# esp32_master_board.net
KiCad netlist of a schematic drawn in EAGLE
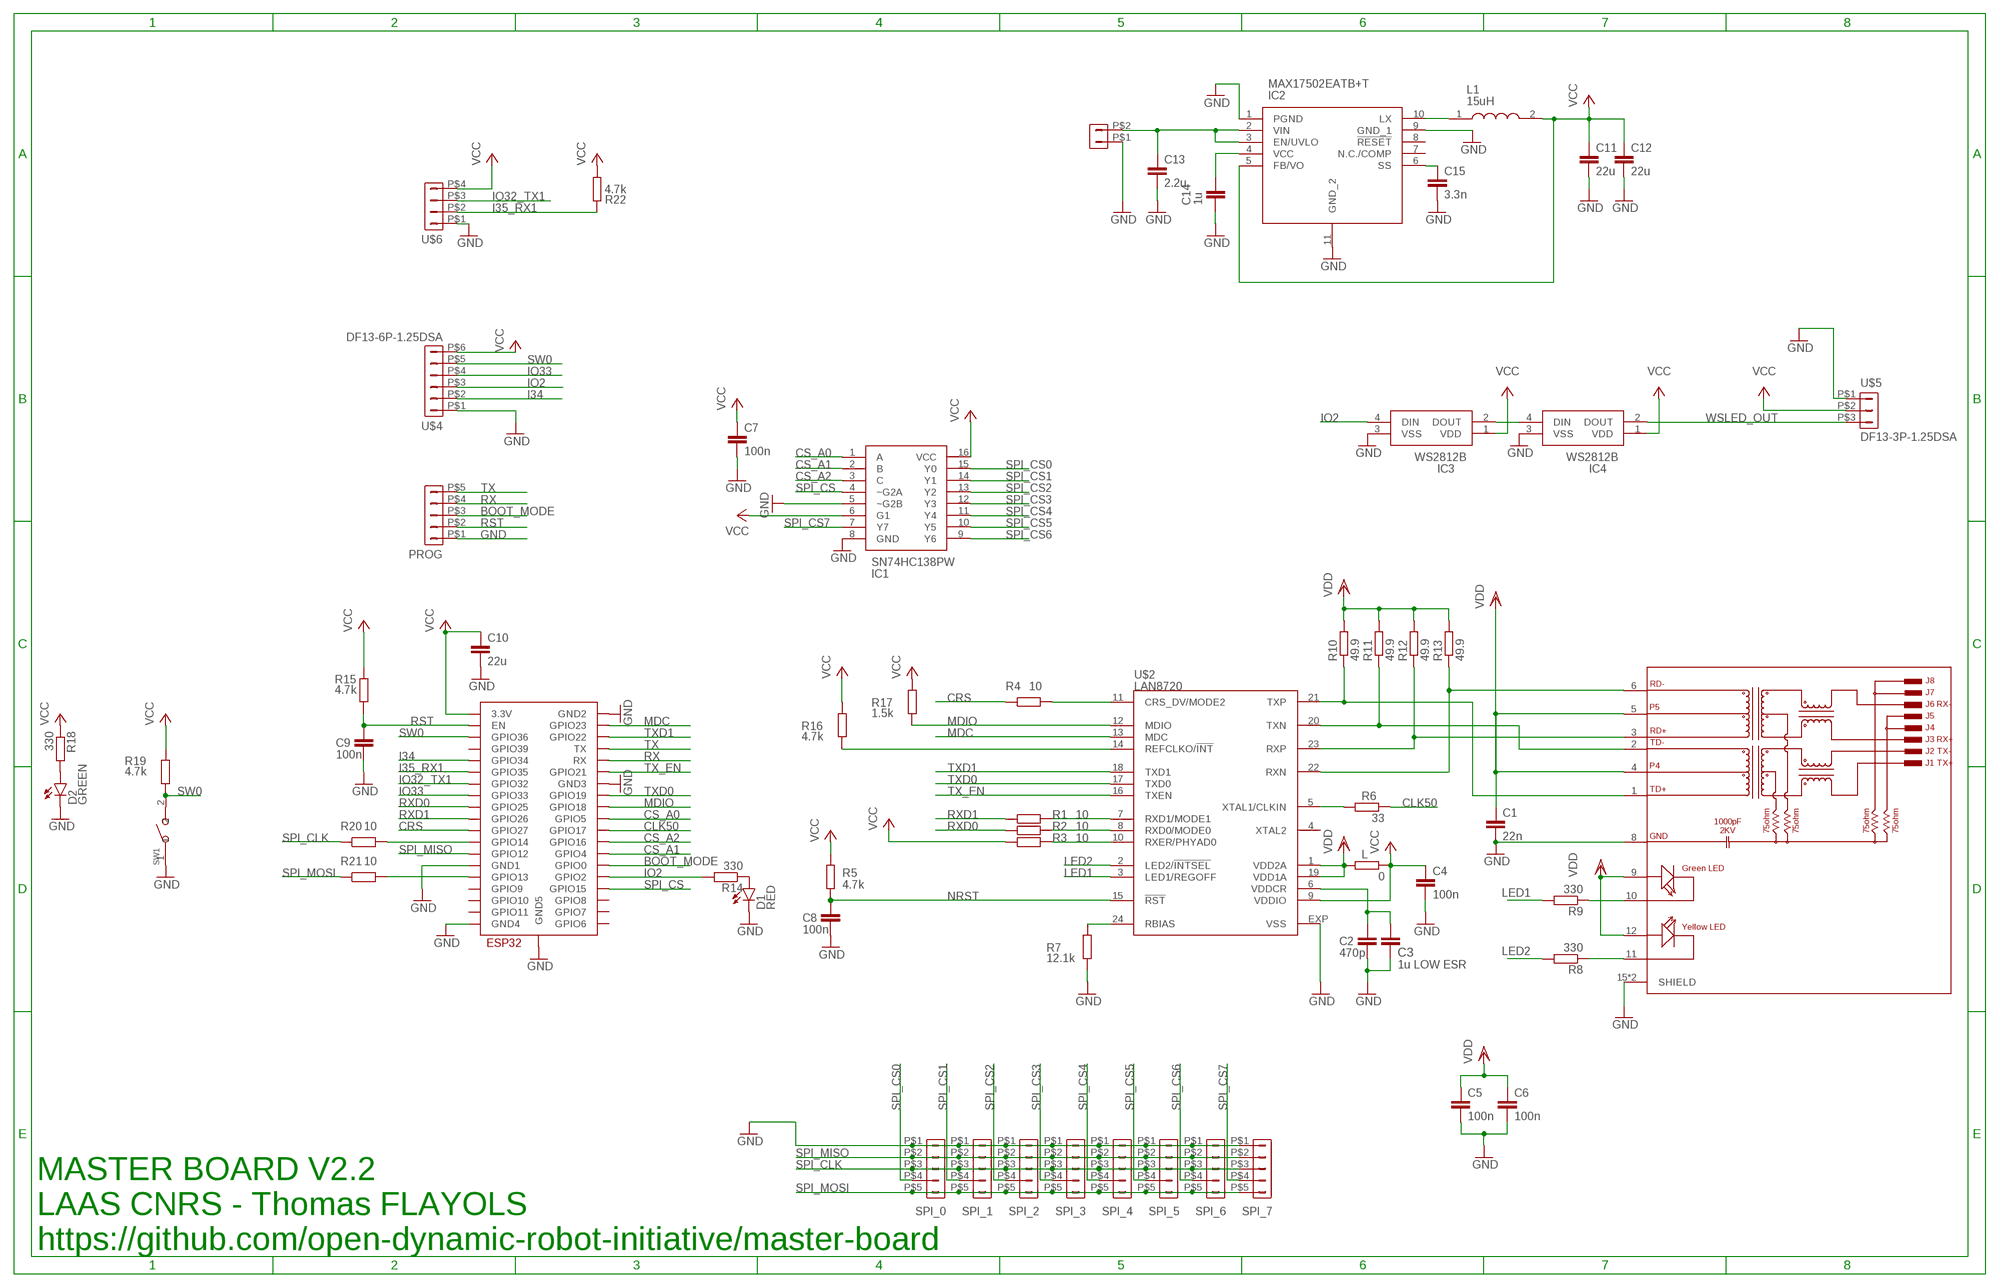
[diagram p0: schematic, sheet 1]

(export (version "E")
  (design (tool "Eeschema 10.0.6"))
  (components
    (comp (ref "C1")
      (value "22n")
      (footprint "eagle-import:0402")
      (fields (field (name "MANUFACTURER_PART_NUMBER") "885012205052"))
      (libsource (lib "eagle-import") (part "resistor_C-EUC0402"))
    )
    (comp (ref "C2")
      (value "470p")
      (footprint "eagle-import:0402")
      (fields (field (name "MANUFACTURER_PART_NUMBER") "CL05C471JB5NNNC"))
      (libsource (lib "eagle-import") (part "resistor_C-EUC0402"))
    )
    (comp (ref "C3")
      (value "1u LOW ESR")
      (footprint "eagle-import:0402")
      (fields (field (name "MANUFACTURER_PART_NUMBER") "CPL-CAP-X5R-0402-1UF-6.3V"))
      (libsource (lib "eagle-import") (part "resistor_C-EUC0402"))
    )
    (comp (ref "C4")
      (value "100n")
      (footprint "eagle-import:0402")
      (fields (field (name "MANUFACTURER_PART_NUMBER") "CPL-CAP-X7R-0402-100NF-16V"))
      (libsource (lib "eagle-import") (part "resistor_C-EUC0402"))
    )
    (comp (ref "C5")
      (value "100n")
      (footprint "eagle-import:0402")
      (fields (field (name "MANUFACTURER_PART_NUMBER") "CPL-CAP-X7R-0402-100NF-16V"))
      (libsource (lib "eagle-import") (part "resistor_C-EUC0402"))
    )
    (comp (ref "C6")
      (value "100n")
      (footprint "eagle-import:0402")
      (fields (field (name "MANUFACTURER_PART_NUMBER") "CPL-CAP-X7R-0402-100NF-16V"))
      (libsource (lib "eagle-import") (part "resistor_C-EUC0402"))
    )
    (comp (ref "C7")
      (value "100n")
      (footprint "eagle-import:0402")
      (fields (field (name "MANUFACTURER_PART_NUMBER") "CPL-CAP-X7R-0402-100NF-16V"))
      (libsource (lib "eagle-import") (part "resistor_C-EUC0402"))
    )
    (comp (ref "C8")
      (value "100n")
      (footprint "eagle-import:0402")
      (fields (field (name "MANUFACTURER_PART_NUMBER") "CPL-CAP-X7R-0402-100NF-16V"))
      (libsource (lib "eagle-import") (part "resistor_C-EUC0402"))
    )
    (comp (ref "C9")
      (value "100n")
      (footprint "eagle-import:0402")
      (fields (field (name "MANUFACTURER_PART_NUMBER") "CPL-CAP-X7R-0402-100NF-16V"))
      (libsource (lib "eagle-import") (part "resistor_C-EUC0402"))
    )
    (comp (ref "C10")
      (value "22u")
      (footprint "eagle-import:C0805")
      (fields (field (name "MANUFACTURER_PART_NUMBER") "CPL-CAP-X5R-0805-22UF-6.3V"))
      (libsource (lib "eagle-import") (part "C-EUC0805"))
    )
    (comp (ref "C11")
      (value "22u")
      (footprint "eagle-import:C0805")
      (fields (field (name "MANUFACTURER_PART_NUMBER") "CPL-CAP-X5R-0805-22UF-6.3V"))
      (libsource (lib "eagle-import") (part "C-EUC0805"))
    )
    (comp (ref "C12")
      (value "22u")
      (footprint "eagle-import:C0805")
      (fields (field (name "MANUFACTURER_PART_NUMBER") "CPL-CAP-X5R-0805-22UF-6.3V"))
      (libsource (lib "eagle-import") (part "C-EUC0805"))
    )
    (comp (ref "C13")
      (value "2.2u")
      (footprint "eagle-import:C1210")
      (fields (field (name "MANUFACTURER_PART_NUMBER") "C3225X7R1H225K250AB"))
      (libsource (lib "eagle-import") (part "resistor_C-EUC1210"))
    )
    (comp (ref "C14")
      (value "1u")
      (footprint "eagle-import:0402")
      (fields (field (name "MANUFACTURER_PART_NUMBER") "CPL-CAP-X5R-0402-1UF-6.3V"))
      (libsource (lib "eagle-import") (part "resistor_C-EUC0402"))
    )
    (comp (ref "C15")
      (value "3.3n")
      (footprint "eagle-import:0402")
      (fields (field (name "MANUFACTURER_PART_NUMBER") "885012205064"))
      (libsource (lib "eagle-import") (part "resistor_C-EUC0402"))
    )
    (comp (ref "D1")
      (value "RED")
      (footprint "eagle-import:CHIPLED_0603")
      (fields (field (name "MANUFACTURER_PART_NUMBER") "CPL-LED-0603-RED"))
      (libsource (lib "eagle-import") (part "LEDCHIPLED_0603"))
    )
    (comp (ref "D2")
      (value "GREEN")
      (footprint "eagle-import:CHIPLED_0603")
      (fields (field (name "MANUFACTURER_PART_NUMBER") "CPL-LED-0603-GREEN"))
      (libsource (lib "eagle-import") (part "LEDCHIPLED_0603"))
    )
    (comp (ref "IC1")
      (value "SN74HC138PW")
      (footprint "eagle-import:SOP65P640X120-16N")
      (fields (field (name "RS_PART_NUMBER") "6631928"))
      (libsource (lib "eagle-import") (part "SN74HC138PW"))
    )
    (comp (ref "IC2")
      (value "MAX17502EATB+T")
      (footprint "eagle-import:SON50P200X300X80-11N")
      (fields (field (name "MOUSER_PART_NUMBER") "700-MAX17502EATB+T"))
      (libsource (lib "eagle-import") (part "MAX17502EATB+T"))
    )
    (comp (ref "IC3")
      (value "WS2812B")
      (footprint "eagle-import:WS2812B")
      (libsource (lib "eagle-import") (part "WS2812B"))
    )
    (comp (ref "IC4")
      (value "WS2812B")
      (footprint "eagle-import:WS2812B")
      (libsource (lib "eagle-import") (part "WS2812B"))
    )
    (comp (ref "L")
      (value "0")
      (footprint "eagle-import:0402")
      (fields (field (name "MANUFACTURER_PART_NUMBER") "CPL-RES-0402-0-0.063W"))
      (libsource (lib "eagle-import") (part "R-EU_R0402"))
    )
    (comp (ref "L1")
      (value "15uH")
      (footprint "eagle-import:LPS6235")
      (fields
        (field (name "MANUFACTURER_PART_NUMBER") "LPS6235-153MRB")
        (field (name "MOUSER_PART_NUMBER") "994-LPS6235-153MRB")
      )
      (libsource (lib "eagle-import") (part "LPS6235-153MRB"))
    )
    (comp (ref "POWER")
      (value "DF13-2P-1.25DSA")
      (footprint "eagle-import:DF13-2P-1.25DSA")
      (fields (field (name "MANUFACTURER_PART_NUMBER") "DF13-3P-1.25DSA"))
      (libsource (lib "eagle-import") (part "DF13-2P-1.25DSA"))
    )
    (comp (ref "PROG")
      (value "DF13-5P-1.25DSA")
      (footprint "eagle-import:DF13-5P-1.25DSA")
      (libsource (lib "eagle-import") (part "DF13-5P-1.25DSA"))
    )
    (comp (ref "R1")
      (value "10")
      (footprint "eagle-import:0402")
      (fields (field (name "MANUFACTURER_PART_NUMBER") "CPL-RES-0402-10-0.063W"))
      (libsource (lib "eagle-import") (part "R-EU_R0402"))
    )
    (comp (ref "R2")
      (value "10")
      (footprint "eagle-import:0402")
      (fields (field (name "MANUFACTURER_PART_NUMBER") "CPL-RES-0402-10-0.063W"))
      (libsource (lib "eagle-import") (part "R-EU_R0402"))
    )
    (comp (ref "R3")
      (value "10")
      (footprint "eagle-import:0402")
      (fields (field (name "MANUFACTURER_PART_NUMBER") "CPL-RES-0402-10-0.063W"))
      (libsource (lib "eagle-import") (part "R-EU_R0402"))
    )
    (comp (ref "R4")
      (value "10")
      (footprint "eagle-import:0402")
      (fields (field (name "MANUFACTURER_PART_NUMBER") "CPL-RES-0402-10-0.063W"))
      (libsource (lib "eagle-import") (part "R-EU_R0402"))
    )
    (comp (ref "R5")
      (value "4.7k")
      (footprint "eagle-import:0402")
      (fields (field (name "MANUFACTURER_PART_NUMBER") "CPL-RES-0402-4.7K-0.063W"))
      (libsource (lib "eagle-import") (part "R-EU_R0402"))
    )
    (comp (ref "R6")
      (value "33")
      (footprint "eagle-import:0402")
      (fields (field (name "MANUFACTURER_PART_NUMBER") "CRCW040233R0FKEDC"))
      (libsource (lib "eagle-import") (part "R-EU_R0402"))
    )
    (comp (ref "R7")
      (value "12.1k")
      (footprint "eagle-import:0402")
      (fields (field (name "MANUFACTURER_PART_NUMBER") "ERJ-U02F1212X"))
      (libsource (lib "eagle-import") (part "R-EU_R0402"))
    )
    (comp (ref "R8")
      (value "330")
      (footprint "eagle-import:0402")
      (fields (field (name "MANUFACTURER_PART_NUMBER") "RC0402JR-13330RL"))
      (libsource (lib "eagle-import") (part "R-EU_R0402"))
    )
    (comp (ref "R9")
      (value "330")
      (footprint "eagle-import:0402")
      (fields (field (name "MANUFACTURER_PART_NUMBER") "RC0402JR-13330RL"))
      (libsource (lib "eagle-import") (part "R-EU_R0402"))
    )
    (comp (ref "R10")
      (value "49.9")
      (footprint "eagle-import:0402")
      (fields (field (name "MANUFACTURER_PART_NUMBER") "CRCW040249R9FKEDC"))
      (libsource (lib "eagle-import") (part "R-EU_R0402"))
    )
    (comp (ref "R11")
      (value "49.9")
      (footprint "eagle-import:0402")
      (fields (field (name "MANUFACTURER_PART_NUMBER") "CRCW040249R9FKEDC"))
      (libsource (lib "eagle-import") (part "R-EU_R0402"))
    )
    (comp (ref "R12")
      (value "49.9")
      (footprint "eagle-import:0402")
      (fields (field (name "MANUFACTURER_PART_NUMBER") "CRCW040249R9FKEDC"))
      (libsource (lib "eagle-import") (part "R-EU_R0402"))
    )
    (comp (ref "R13")
      (value "49.9")
      (footprint "eagle-import:0402")
      (fields (field (name "MANUFACTURER_PART_NUMBER") "CRCW040249R9FKEDC"))
      (libsource (lib "eagle-import") (part "R-EU_R0402"))
    )
    (comp (ref "R14")
      (value "330")
      (footprint "eagle-import:0402")
      (fields (field (name "MANUFACTURER_PART_NUMBER") "RC0402JR-13330RL"))
      (libsource (lib "eagle-import") (part "R-EU_R0402"))
    )
    (comp (ref "R15")
      (value "4.7k")
      (footprint "eagle-import:0402")
      (fields (field (name "MANUFACTURER_PART_NUMBER") "CPL-RES-0402-4.7K-0.063W"))
      (libsource (lib "eagle-import") (part "R-EU_R0402"))
    )
    (comp (ref "R16")
      (value "4.7k")
      (footprint "eagle-import:0402")
      (fields (field (name "MANUFACTURER_PART_NUMBER") "CPL-RES-0402-4.7K-0.063W"))
      (libsource (lib "eagle-import") (part "R-EU_R0402"))
    )
    (comp (ref "R17")
      (value "1.5k")
      (footprint "eagle-import:0402")
      (fields (field (name "MANUFACTURER_PART_NUMBER") "ERJ2GEJ152X"))
      (libsource (lib "eagle-import") (part "R-EU_R0402"))
    )
    (comp (ref "R18")
      (value "330")
      (footprint "eagle-import:0402")
      (fields (field (name "MANUFACTURER_PART_NUMBER") "RC0402JR-13330RL"))
      (libsource (lib "eagle-import") (part "R-EU_R0402"))
    )
    (comp (ref "R19")
      (value "4.7k")
      (footprint "eagle-import:0402")
      (fields (field (name "MANUFACTURER_PART_NUMBER") "CPL-RES-0402-4.7K-0.063W"))
      (libsource (lib "eagle-import") (part "R-EU_R0402"))
    )
    (comp (ref "R20")
      (value "10")
      (footprint "eagle-import:0402")
      (fields (field (name "MANUFACTURER_PART_NUMBER") "CPL-RES-0402-10-0.063W"))
      (libsource (lib "eagle-import") (part "R-EU_R0402"))
    )
    (comp (ref "R21")
      (value "10")
      (footprint "eagle-import:0402")
      (fields (field (name "MANUFACTURER_PART_NUMBER") "CPL-RES-0402-10-0.063W"))
      (libsource (lib "eagle-import") (part "R-EU_R0402"))
    )
    (comp (ref "R22")
      (value "4.7k")
      (footprint "eagle-import:0402")
      (fields (field (name "MANUFACTURER_PART_NUMBER") "CPL-RES-0402-4.7K-0.063W"))
      (libsource (lib "eagle-import") (part "R-EU_R0402"))
    )
    (comp (ref "SPI_0")
      (value "DF13-5P-1.25DSA")
      (footprint "eagle-import:DF13-5P-1.25DSA")
      (libsource (lib "eagle-import") (part "DF13-5P-1.25DSA"))
    )
    (comp (ref "SPI_1")
      (value "DF13-5P-1.25DSA")
      (footprint "eagle-import:DF13-5P-1.25DSA")
      (libsource (lib "eagle-import") (part "DF13-5P-1.25DSA"))
    )
    (comp (ref "SPI_2")
      (value "DF13-5P-1.25DSA")
      (footprint "eagle-import:DF13-5P-1.25DSA")
      (libsource (lib "eagle-import") (part "DF13-5P-1.25DSA"))
    )
    (comp (ref "SPI_3")
      (value "DF13-5P-1.25DSA")
      (footprint "eagle-import:DF13-5P-1.25DSA")
      (libsource (lib "eagle-import") (part "DF13-5P-1.25DSA"))
    )
    (comp (ref "SPI_4")
      (value "DF13-5P-1.25DSA")
      (footprint "eagle-import:DF13-5P-1.25DSA")
      (libsource (lib "eagle-import") (part "DF13-5P-1.25DSA"))
    )
    (comp (ref "SPI_5")
      (value "DF13-5P-1.25DSA")
      (footprint "eagle-import:DF13-5P-1.25DSA")
      (libsource (lib "eagle-import") (part "DF13-5P-1.25DSA"))
    )
    (comp (ref "SPI_6")
      (value "DF13-5P-1.25DSA")
      (footprint "eagle-import:DF13-5P-1.25DSA")
      (libsource (lib "eagle-import") (part "DF13-5P-1.25DSA"))
    )
    (comp (ref "SPI_7")
      (value "DF13-5P-1.25DSA")
      (footprint "eagle-import:DF13-5P-1.25DSA")
      (libsource (lib "eagle-import") (part "DF13-5P-1.25DSA"))
    )
    (comp (ref "SW1")
      (value "B3U-1000P-2P-SMD")
      (footprint "eagle-import:SW2-2.6-3.0X2.5X1.2+0.4MM")
      (fields (field (name "MANUFACTURER_PART_NUMBER") "B3U-1000P"))
      (libsource (lib "eagle-import") (part "SMD-BUTTON(2P-3.0X2.5X1.2+0.4MM)-B3U-1000P-2P-SMD"))
    )
    (comp (ref "U$1")
      (value "ESP32-WROOM")
      (footprint "eagle-import:ESP32-WROOM")
      (fields (field (name "MANUFACTURER_PART_NUMBER") "ESP32-WROOM-32D"))
      (libsource (lib "eagle-import") (part "ESP32-WROOM"))
    )
    (comp (ref "U$2")
      (value "LAN8720")
      (footprint "eagle-import:QFN24")
      (fields (field (name "MANUFACTURER_PART_NUMBER") "LAN8720A-CP"))
      (libsource (lib "eagle-import") (part "LAN8720"))
    )
    (comp (ref "U$3")
      (value "HR911105A")
      (footprint "eagle-import:HANRUN_HR911105A")
      (fields (field (name "MF") "DFRobot"))
      (libsource (lib "eagle-import") (part "HR911105A"))
    )
    (comp (ref "U$4")
      (value "DF13-6P-1.25DSA")
      (footprint "eagle-import:DF13-6P-1.25DSA")
      (libsource (lib "eagle-import") (part "DF13-6P-1.25DSA"))
    )
    (comp (ref "U$5")
      (value "DF13-3P-1.25DSA")
      (footprint "eagle-import:DF13-3P-1.25DSA")
      (libsource (lib "eagle-import") (part "DF13-3P-1.25DSA"))
    )
    (comp (ref "U$6")
      (value "DF13-4P-1.25DSA")
      (footprint "eagle-import:DF13-4P-1.25DSA")
      (libsource (lib "eagle-import") (part "DF13-4P-1.25DSA"))
    )
  )
  (nets
    (net (code "1") (name "/BOOT_MODE") (class "Default")
      (node (ref "PROG") (pin "P$3") (pinfunction "3_P$3") (pintype "passive"))
      (node (ref "U$1") (pin "IO0") (pinfunction "GPIO0_IO0") (pintype "bidirectional"))
    )
    (net (code "2") (name "/CLK50") (class "Default")
      (node (ref "R6") (pin "1") (pinfunction "1_1") (pintype "passive"))
      (node (ref "U$1") (pin "IO17") (pinfunction "GPIO17_IO17") (pintype "bidirectional"))
    )
    (net (code "3") (name "/CRS") (class "Default")
      (node (ref "R4") (pin "1") (pinfunction "1_1") (pintype "passive"))
      (node (ref "U$1") (pin "IO27") (pinfunction "GPIO27_IO27") (pintype "bidirectional"))
    )
    (net (code "4") (name "/CS_A0") (class "Default")
      (node (ref "IC1") (pin "1") (pinfunction "A_1") (pintype "bidirectional"))
      (node (ref "U$1") (pin "IO5") (pinfunction "GPIO5_IO5") (pintype "bidirectional"))
    )
    (net (code "5") (name "/CS_A1") (class "Default")
      (node (ref "IC1") (pin "2") (pinfunction "B_2") (pintype "bidirectional"))
      (node (ref "U$1") (pin "IO4") (pinfunction "GPIO4_IO4") (pintype "bidirectional"))
    )
    (net (code "6") (name "/CS_A2") (class "Default")
      (node (ref "IC1") (pin "3") (pinfunction "C_3") (pintype "bidirectional"))
      (node (ref "U$1") (pin "IO16") (pinfunction "GPIO16_IO16") (pintype "bidirectional"))
    )
    (net (code "7") (name "/I34") (class "Default")
      (node (ref "U$1") (pin "IO34") (pinfunction "GPIO34_IO34") (pintype "bidirectional"))
      (node (ref "U$4") (pin "P$2") (pinfunction "2_P$2") (pintype "passive"))
    )
    (net (code "8") (name "/I35_RX1") (class "Default")
      (node (ref "R22") (pin "2") (pinfunction "2_2") (pintype "passive"))
      (node (ref "U$1") (pin "IO35") (pinfunction "GPIO35_IO35") (pintype "bidirectional"))
      (node (ref "U$6") (pin "P$2") (pinfunction "2_P$2") (pintype "passive"))
    )
    (net (code "9") (name "/IO2") (class "Default")
      (node (ref "IC3") (pin "4") (pinfunction "DIN_4") (pintype "input"))
      (node (ref "R14") (pin "2") (pinfunction "2_2") (pintype "passive"))
      (node (ref "U$1") (pin "IO2") (pinfunction "GPIO2_IO2") (pintype "bidirectional"))
      (node (ref "U$4") (pin "P$3") (pinfunction "3_P$3") (pintype "passive"))
    )
    (net (code "10") (name "/IO32_TX1") (class "Default")
      (node (ref "U$1") (pin "IO32") (pinfunction "GPIO32_IO32") (pintype "bidirectional"))
      (node (ref "U$6") (pin "P$3") (pinfunction "3_P$3") (pintype "passive"))
    )
    (net (code "11") (name "/IO33") (class "Default")
      (node (ref "U$1") (pin "IO33") (pinfunction "GPIO33_IO33") (pintype "bidirectional"))
      (node (ref "U$4") (pin "P$4") (pinfunction "4_P$4") (pintype "passive"))
    )
    (net (code "12") (name "/LED1") (class "Default")
      (node (ref "R9") (pin "2") (pinfunction "2_2") (pintype "passive"))
      (node (ref "U$2") (pin "3") (pinfunction "LED1/REGOFF_3") (pintype "bidirectional"))
    )
    (net (code "13") (name "/LED2") (class "Default")
      (node (ref "R8") (pin "2") (pinfunction "2_2") (pintype "passive"))
      (node (ref "U$2") (pin "2") (pinfunction "LED2/~{INTSEL}_2") (pintype "bidirectional"))
    )
    (net (code "14") (name "/MDC") (class "Default")
      (node (ref "U$1") (pin "IO23") (pinfunction "GPIO23_IO23") (pintype "bidirectional"))
      (node (ref "U$2") (pin "13") (pinfunction "MDC_13") (pintype "bidirectional"))
    )
    (net (code "15") (name "/MDIO") (class "Default")
      (node (ref "R17") (pin "1") (pinfunction "1_1") (pintype "passive"))
      (node (ref "U$1") (pin "IO18") (pinfunction "GPIO18_IO18") (pintype "bidirectional"))
      (node (ref "U$2") (pin "12") (pinfunction "MDIO_12") (pintype "bidirectional"))
    )
    (net (code "16") (name "/NRST") (class "Default")
      (node (ref "C8") (pin "1") (pinfunction "1_1") (pintype "passive"))
      (node (ref "R5") (pin "1") (pinfunction "1_1") (pintype "passive"))
      (node (ref "U$2") (pin "15") (pinfunction "~{RST}_15") (pintype "bidirectional"))
    )
    (net (code "17") (name "/RST") (class "Default")
      (node (ref "C9") (pin "1") (pinfunction "1_1") (pintype "passive"))
      (node (ref "PROG") (pin "P$2") (pinfunction "2_P$2") (pintype "passive"))
      (node (ref "R15") (pin "1") (pinfunction "1_1") (pintype "passive"))
      (node (ref "U$1") (pin "EN") (pinfunction "EN_EN") (pintype "bidirectional"))
    )
    (net (code "18") (name "/RX") (class "Default")
      (node (ref "PROG") (pin "P$4") (pinfunction "4_P$4") (pintype "passive"))
      (node (ref "U$1") (pin "RX") (pinfunction "RX_RX") (pintype "bidirectional"))
    )
    (net (code "19") (name "/RXD0") (class "Default")
      (node (ref "R2") (pin "1") (pinfunction "1_1") (pintype "passive"))
      (node (ref "U$1") (pin "IO25") (pinfunction "GPIO25_IO25") (pintype "bidirectional"))
    )
    (net (code "20") (name "/RXD1") (class "Default")
      (node (ref "R1") (pin "1") (pinfunction "1_1") (pintype "passive"))
      (node (ref "U$1") (pin "IO26") (pinfunction "GPIO26_IO26") (pintype "bidirectional"))
    )
    (net (code "21") (name "/SPI_CLK") (class "Default")
      (node (ref "R20") (pin "1") (pinfunction "1_1") (pintype "passive"))
      (node (ref "SPI_0") (pin "P$3") (pinfunction "3_P$3") (pintype "passive"))
      (node (ref "SPI_1") (pin "P$3") (pinfunction "3_P$3") (pintype "passive"))
      (node (ref "SPI_2") (pin "P$3") (pinfunction "3_P$3") (pintype "passive"))
      (node (ref "SPI_3") (pin "P$3") (pinfunction "3_P$3") (pintype "passive"))
      (node (ref "SPI_4") (pin "P$3") (pinfunction "3_P$3") (pintype "passive"))
      (node (ref "SPI_5") (pin "P$3") (pinfunction "3_P$3") (pintype "passive"))
      (node (ref "SPI_6") (pin "P$3") (pinfunction "3_P$3") (pintype "passive"))
      (node (ref "SPI_7") (pin "P$3") (pinfunction "3_P$3") (pintype "passive"))
    )
    (net (code "22") (name "/SPI_CS") (class "Default")
      (node (ref "IC1") (pin "4") (pinfunction "~{G2A}_4") (pintype "bidirectional"))
      (node (ref "U$1") (pin "IO15") (pinfunction "GPIO15_IO15") (pintype "bidirectional"))
    )
    (net (code "23") (name "/SPI_CS0") (class "Default")
      (node (ref "IC1") (pin "15") (pinfunction "Y0_15") (pintype "bidirectional"))
      (node (ref "SPI_0") (pin "P$4") (pinfunction "4_P$4") (pintype "passive"))
    )
    (net (code "24") (name "/SPI_CS1") (class "Default")
      (node (ref "IC1") (pin "14") (pinfunction "Y1_14") (pintype "bidirectional"))
      (node (ref "SPI_1") (pin "P$4") (pinfunction "4_P$4") (pintype "passive"))
    )
    (net (code "25") (name "/SPI_CS2") (class "Default")
      (node (ref "IC1") (pin "13") (pinfunction "Y2_13") (pintype "bidirectional"))
      (node (ref "SPI_2") (pin "P$4") (pinfunction "4_P$4") (pintype "passive"))
    )
    (net (code "26") (name "/SPI_CS3") (class "Default")
      (node (ref "IC1") (pin "12") (pinfunction "Y3_12") (pintype "bidirectional"))
      (node (ref "SPI_3") (pin "P$4") (pinfunction "4_P$4") (pintype "passive"))
    )
    (net (code "27") (name "/SPI_CS4") (class "Default")
      (node (ref "IC1") (pin "11") (pinfunction "Y4_11") (pintype "bidirectional"))
      (node (ref "SPI_4") (pin "P$4") (pinfunction "4_P$4") (pintype "passive"))
    )
    (net (code "28") (name "/SPI_CS5") (class "Default")
      (node (ref "IC1") (pin "10") (pinfunction "Y5_10") (pintype "bidirectional"))
      (node (ref "SPI_5") (pin "P$4") (pinfunction "4_P$4") (pintype "passive"))
    )
    (net (code "29") (name "/SPI_CS6") (class "Default")
      (node (ref "IC1") (pin "9") (pinfunction "Y6_9") (pintype "bidirectional"))
      (node (ref "SPI_6") (pin "P$4") (pinfunction "4_P$4") (pintype "passive"))
    )
    (net (code "30") (name "/SPI_CS7") (class "Default")
      (node (ref "IC1") (pin "7") (pinfunction "Y7_7") (pintype "bidirectional"))
      (node (ref "SPI_7") (pin "P$4") (pinfunction "4_P$4") (pintype "passive"))
    )
    (net (code "31") (name "/SPI_MISO") (class "Default")
      (node (ref "SPI_0") (pin "P$2") (pinfunction "2_P$2") (pintype "passive"))
      (node (ref "SPI_1") (pin "P$2") (pinfunction "2_P$2") (pintype "passive"))
      (node (ref "SPI_2") (pin "P$2") (pinfunction "2_P$2") (pintype "passive"))
      (node (ref "SPI_3") (pin "P$2") (pinfunction "2_P$2") (pintype "passive"))
      (node (ref "SPI_4") (pin "P$2") (pinfunction "2_P$2") (pintype "passive"))
      (node (ref "SPI_5") (pin "P$2") (pinfunction "2_P$2") (pintype "passive"))
      (node (ref "SPI_6") (pin "P$2") (pinfunction "2_P$2") (pintype "passive"))
      (node (ref "SPI_7") (pin "P$2") (pinfunction "2_P$2") (pintype "passive"))
      (node (ref "U$1") (pin "IO12") (pinfunction "GPIO12_IO12") (pintype "bidirectional"))
    )
    (net (code "32") (name "/SPI_MOSI") (class "Default")
      (node (ref "R21") (pin "1") (pinfunction "1_1") (pintype "passive"))
      (node (ref "SPI_0") (pin "P$5") (pinfunction "5_P$5") (pintype "passive"))
      (node (ref "SPI_1") (pin "P$5") (pinfunction "5_P$5") (pintype "passive"))
      (node (ref "SPI_2") (pin "P$5") (pinfunction "5_P$5") (pintype "passive"))
      (node (ref "SPI_3") (pin "P$5") (pinfunction "5_P$5") (pintype "passive"))
      (node (ref "SPI_4") (pin "P$5") (pinfunction "5_P$5") (pintype "passive"))
      (node (ref "SPI_5") (pin "P$5") (pinfunction "5_P$5") (pintype "passive"))
      (node (ref "SPI_6") (pin "P$5") (pinfunction "5_P$5") (pintype "passive"))
      (node (ref "SPI_7") (pin "P$5") (pinfunction "5_P$5") (pintype "passive"))
    )
    (net (code "33") (name "/SW0") (class "Default")
      (node (ref "R19") (pin "1") (pinfunction "1_1") (pintype "passive"))
      (node (ref "SW1") (pin "2") (pinfunction "2_2") (pintype "bidirectional"))
      (node (ref "U$1") (pin "SENSOR_VP") (pinfunction "GPIO36_SENSOR_VP") (pintype "bidirectional"))
      (node (ref "U$4") (pin "P$5") (pinfunction "5_P$5") (pintype "passive"))
    )
    (net (code "34") (name "/TX") (class "Default")
      (node (ref "PROG") (pin "P$5") (pinfunction "5_P$5") (pintype "passive"))
      (node (ref "U$1") (pin "TX") (pinfunction "TX_TX") (pintype "bidirectional"))
    )
    (net (code "35") (name "/TXD0") (class "Default")
      (node (ref "U$1") (pin "IO19") (pinfunction "GPIO19_IO19") (pintype "bidirectional"))
      (node (ref "U$2") (pin "17") (pinfunction "TXD0_17") (pintype "bidirectional"))
    )
    (net (code "36") (name "/TXD1") (class "Default")
      (node (ref "U$1") (pin "IO22") (pinfunction "GPIO22_IO22") (pintype "bidirectional"))
      (node (ref "U$2") (pin "18") (pinfunction "TXD1_18") (pintype "bidirectional"))
    )
    (net (code "37") (name "/TX_EN") (class "Default")
      (node (ref "U$1") (pin "IO21") (pinfunction "GPIO21_IO21") (pintype "bidirectional"))
      (node (ref "U$2") (pin "16") (pinfunction "TXEN_16") (pintype "bidirectional"))
    )
    (net (code "38") (name "/WSLED_OUT") (class "Default")
      (node (ref "IC4") (pin "2") (pinfunction "DOUT_2") (pintype "output"))
      (node (ref "U$5") (pin "P$3") (pinfunction "3_P$3") (pintype "passive"))
    )
    (net (code "39") (name "GND") (class "Default")
      (node (ref "C1") (pin "2") (pinfunction "2_2") (pintype "passive"))
      (node (ref "C10") (pin "2") (pinfunction "2_2") (pintype "passive"))
      (node (ref "C11") (pin "2") (pinfunction "2_2") (pintype "passive"))
      (node (ref "C12") (pin "2") (pinfunction "2_2") (pintype "passive"))
      (node (ref "C13") (pin "2") (pinfunction "2_2") (pintype "passive"))
      (node (ref "C14") (pin "1") (pinfunction "1_1") (pintype "passive"))
      (node (ref "C15") (pin "2") (pinfunction "2_2") (pintype "passive"))
      (node (ref "C2") (pin "2") (pinfunction "2_2") (pintype "passive"))
      (node (ref "C3") (pin "2") (pinfunction "2_2") (pintype "passive"))
      (node (ref "C4") (pin "2") (pinfunction "2_2") (pintype "passive"))
      (node (ref "C5") (pin "2") (pinfunction "2_2") (pintype "passive"))
      (node (ref "C6") (pin "2") (pinfunction "2_2") (pintype "passive"))
      (node (ref "C7") (pin "2") (pinfunction "2_2") (pintype "passive"))
      (node (ref "C8") (pin "2") (pinfunction "2_2") (pintype "passive"))
      (node (ref "C9") (pin "2") (pinfunction "2_2") (pintype "passive"))
      (node (ref "D1") (pin "C") (pinfunction "C_C") (pintype "passive"))
      (node (ref "D2") (pin "C") (pinfunction "C_C") (pintype "passive"))
      (node (ref "IC1") (pin "5") (pinfunction "~{G2B}_5") (pintype "bidirectional"))
      (node (ref "IC1") (pin "8") (pinfunction "GND_8") (pintype "bidirectional"))
      (node (ref "IC2") (pin "1") (pinfunction "PGND_1") (pintype "bidirectional"))
      (node (ref "IC2") (pin "11") (pinfunction "GND_2_11") (pintype "bidirectional"))
      (node (ref "IC2") (pin "9") (pinfunction "GND_1_9") (pintype "bidirectional"))
      (node (ref "IC3") (pin "3") (pinfunction "VSS_3") (pintype "power_in"))
      (node (ref "IC4") (pin "3") (pinfunction "VSS_3") (pintype "power_in"))
      (node (ref "POWER") (pin "P$1") (pinfunction "1_P$1") (pintype "passive"))
      (node (ref "PROG") (pin "P$1") (pinfunction "1_P$1") (pintype "passive"))
      (node (ref "R7") (pin "1") (pinfunction "1_1") (pintype "passive"))
      (node (ref "SPI_0") (pin "P$1") (pinfunction "1_P$1") (pintype "passive"))
      (node (ref "SPI_1") (pin "P$1") (pinfunction "1_P$1") (pintype "passive"))
      (node (ref "SPI_2") (pin "P$1") (pinfunction "1_P$1") (pintype "passive"))
      (node (ref "SPI_3") (pin "P$1") (pinfunction "1_P$1") (pintype "passive"))
      (node (ref "SPI_4") (pin "P$1") (pinfunction "1_P$1") (pintype "passive"))
      (node (ref "SPI_5") (pin "P$1") (pinfunction "1_P$1") (pintype "passive"))
      (node (ref "SPI_6") (pin "P$1") (pinfunction "1_P$1") (pintype "passive"))
      (node (ref "SPI_7") (pin "P$1") (pinfunction "1_P$1") (pintype "passive"))
      (node (ref "SW1") (pin "1") (pinfunction "1_1") (pintype "bidirectional"))
      (node (ref "U$1") (pin "GND1") (pinfunction "GND1_GND1") (pintype "bidirectional"))
      (node (ref "U$1") (pin "GND2") (pinfunction "GND2_GND2") (pintype "bidirectional"))
      (node (ref "U$1") (pin "GND3") (pinfunction "GND3_GND3") (pintype "bidirectional"))
      (node (ref "U$1") (pin "GND4") (pinfunction "GND4_GND4") (pintype "bidirectional"))
      (node (ref "U$1") (pin "GND5") (pinfunction "GND5_GND5") (pintype "bidirectional"))
      (node (ref "U$2") (pin "EXP") (pinfunction "VSS_EXP") (pintype "power_in"))
      (node (ref "U$3") (pin "15") (pinfunction "SHIELD_15") (pintype "passive"))
      (node (ref "U$3") (pin "16") (pinfunction "SHIELD_16") (pintype "passive"))
      (node (ref "U$3") (pin "8") (pinfunction "GND_8") (pintype "power_in"))
      (node (ref "U$4") (pin "P$1") (pinfunction "1_P$1") (pintype "passive"))
      (node (ref "U$5") (pin "P$1") (pinfunction "1_P$1") (pintype "passive"))
      (node (ref "U$6") (pin "P$1") (pinfunction "1_P$1") (pintype "passive"))
    )
    (net (code "40") (name "Net-(D1-PadA)") (class "Default")
      (node (ref "D1") (pin "A") (pinfunction "A_A") (pintype "passive"))
      (node (ref "R14") (pin "1") (pinfunction "1_1") (pintype "passive"))
    )
    (net (code "41") (name "Net-(D2-PadA)") (class "Default")
      (node (ref "D2") (pin "A") (pinfunction "A_A") (pintype "passive"))
      (node (ref "R18") (pin "2") (pinfunction "2_2") (pintype "passive"))
    )
    (net (code "42") (name "Net-(IC2-EN{slash}UVLO)") (class "Default")
      (node (ref "C13") (pin "1") (pinfunction "1_1") (pintype "passive"))
      (node (ref "IC2") (pin "2") (pinfunction "VIN_2") (pintype "bidirectional"))
      (node (ref "IC2") (pin "3") (pinfunction "EN/UVLO_3") (pintype "bidirectional"))
      (node (ref "POWER") (pin "P$2") (pinfunction "2_P$2") (pintype "passive"))
    )
    (net (code "43") (name "Net-(IC2-LX)") (class "Default")
      (node (ref "IC2") (pin "10") (pinfunction "LX_10") (pintype "bidirectional"))
      (node (ref "L1") (pin "1") (pinfunction "1_1") (pintype "bidirectional"))
    )
    (net (code "44") (name "Net-(IC2-SS)") (class "Default")
      (node (ref "C15") (pin "1") (pinfunction "1_1") (pintype "passive"))
      (node (ref "IC2") (pin "6") (pinfunction "SS_6") (pintype "bidirectional"))
    )
    (net (code "45") (name "Net-(IC2-VCC)") (class "Default")
      (node (ref "C14") (pin "2") (pinfunction "2_2") (pintype "passive"))
      (node (ref "IC2") (pin "4") (pinfunction "VCC_4") (pintype "bidirectional"))
    )
    (net (code "46") (name "Net-(IC3-DOUT)") (class "Default")
      (node (ref "IC3") (pin "2") (pinfunction "DOUT_2") (pintype "output"))
      (node (ref "IC4") (pin "4") (pinfunction "DIN_4") (pintype "input"))
    )
    (net (code "47") (name "Net-(U$1-GPIO13)") (class "Default")
      (node (ref "R21") (pin "2") (pinfunction "2_2") (pintype "passive"))
      (node (ref "U$1") (pin "IO13") (pinfunction "GPIO13_IO13") (pintype "bidirectional"))
    )
    (net (code "48") (name "Net-(U$1-GPIO14)") (class "Default")
      (node (ref "R20") (pin "2") (pinfunction "2_2") (pintype "passive"))
      (node (ref "U$1") (pin "IO14") (pinfunction "GPIO14_IO14") (pintype "bidirectional"))
    )
    (net (code "49") (name "Net-(U$2-CRS_DV{slash}MODE2)") (class "Default")
      (node (ref "R4") (pin "2") (pinfunction "2_2") (pintype "passive"))
      (node (ref "U$2") (pin "11") (pinfunction "CRS_DV/MODE2_11") (pintype "bidirectional"))
    )
    (net (code "50") (name "Net-(U$2-RBIAS)") (class "Default")
      (node (ref "R7") (pin "2") (pinfunction "2_2") (pintype "passive"))
      (node (ref "U$2") (pin "24") (pinfunction "RBIAS_24") (pintype "bidirectional"))
    )
    (net (code "51") (name "Net-(U$2-REFCLKO{slash}~{INT})") (class "Default")
      (node (ref "R16") (pin "1") (pinfunction "1_1") (pintype "passive"))
      (node (ref "U$2") (pin "14") (pinfunction "REFCLKO/~{INT}_14") (pintype "bidirectional"))
    )
    (net (code "52") (name "Net-(U$2-RXD0{slash}MODE0)") (class "Default")
      (node (ref "R2") (pin "2") (pinfunction "2_2") (pintype "passive"))
      (node (ref "U$2") (pin "8") (pinfunction "RXD0/MODE0_8") (pintype "bidirectional"))
    )
    (net (code "53") (name "Net-(U$2-RXD1{slash}MODE1)") (class "Default")
      (node (ref "R1") (pin "2") (pinfunction "2_2") (pintype "passive"))
      (node (ref "U$2") (pin "7") (pinfunction "RXD1/MODE1_7") (pintype "bidirectional"))
    )
    (net (code "54") (name "Net-(U$2-RXER{slash}PHYAD0)") (class "Default")
      (node (ref "R3") (pin "2") (pinfunction "2_2") (pintype "passive"))
      (node (ref "U$2") (pin "10") (pinfunction "RXER/PHYAD0_10") (pintype "bidirectional"))
    )
    (net (code "55") (name "Net-(U$2-RXN)") (class "Default")
      (node (ref "R13") (pin "1") (pinfunction "1_1") (pintype "passive"))
      (node (ref "U$2") (pin "22") (pinfunction "RXN_22") (pintype "bidirectional"))
      (node (ref "U$3") (pin "6") (pinfunction "RD-_6") (pintype "passive"))
    )
    (net (code "56") (name "Net-(U$2-RXP)") (class "Default")
      (node (ref "R12") (pin "1") (pinfunction "1_1") (pintype "passive"))
      (node (ref "U$2") (pin "23") (pinfunction "RXP_23") (pintype "bidirectional"))
      (node (ref "U$3") (pin "3") (pinfunction "RD+_3") (pintype "passive"))
    )
    (net (code "57") (name "Net-(U$2-TXN)") (class "Default")
      (node (ref "R11") (pin "1") (pinfunction "1_1") (pintype "passive"))
      (node (ref "U$2") (pin "20") (pinfunction "TXN_20") (pintype "bidirectional"))
      (node (ref "U$3") (pin "2") (pinfunction "TD-_2") (pintype "passive"))
    )
    (net (code "58") (name "Net-(U$2-TXP)") (class "Default")
      (node (ref "R10") (pin "1") (pinfunction "1_1") (pintype "passive"))
      (node (ref "U$2") (pin "21") (pinfunction "TXP_21") (pintype "bidirectional"))
      (node (ref "U$3") (pin "1") (pinfunction "TD+_1") (pintype "passive"))
    )
    (net (code "59") (name "Net-(U$2-VDDCR)") (class "Default")
      (node (ref "C2") (pin "1") (pinfunction "1_1") (pintype "passive"))
      (node (ref "C3") (pin "1") (pinfunction "1_1") (pintype "passive"))
      (node (ref "U$2") (pin "6") (pinfunction "VDDCR_6") (pintype "power_in"))
    )
    (net (code "60") (name "Net-(U$2-XTAL1{slash}CLKIN)") (class "Default")
      (node (ref "R6") (pin "2") (pinfunction "2_2") (pintype "passive"))
      (node (ref "U$2") (pin "5") (pinfunction "XTAL1/CLKIN_5") (pintype "bidirectional"))
    )
    (net (code "61") (name "Net-(U$3-GC)") (class "Default")
      (node (ref "R9") (pin "1") (pinfunction "1_1") (pintype "passive"))
      (node (ref "U$3") (pin "10") (pinfunction "GC_10") (pintype "passive"))
    )
    (net (code "62") (name "Net-(U$3-YC)") (class "Default")
      (node (ref "R8") (pin "1") (pinfunction "1_1") (pintype "passive"))
      (node (ref "U$3") (pin "11") (pinfunction "YC_11") (pintype "passive"))
    )
    (net (code "63") (name "VCC") (class "Default")
      (node (ref "C10") (pin "1") (pinfunction "1_1") (pintype "passive"))
      (node (ref "C11") (pin "1") (pinfunction "1_1") (pintype "passive"))
      (node (ref "C12") (pin "1") (pinfunction "1_1") (pintype "passive"))
      (node (ref "C4") (pin "1") (pinfunction "1_1") (pintype "passive"))
      (node (ref "C7") (pin "1") (pinfunction "1_1") (pintype "passive"))
      (node (ref "IC1") (pin "16") (pinfunction "VCC_16") (pintype "bidirectional"))
      (node (ref "IC1") (pin "6") (pinfunction "G1_6") (pintype "bidirectional"))
      (node (ref "IC2") (pin "5") (pinfunction "FB/VO_5") (pintype "bidirectional"))
      (node (ref "IC3") (pin "1") (pinfunction "VDD_1") (pintype "power_in"))
      (node (ref "IC4") (pin "1") (pinfunction "VDD_1") (pintype "power_in"))
      (node (ref "L") (pin "1") (pinfunction "1_1") (pintype "passive"))
      (node (ref "L1") (pin "2") (pinfunction "2_2") (pintype "bidirectional"))
      (node (ref "R15") (pin "2") (pinfunction "2_2") (pintype "passive"))
      (node (ref "R16") (pin "2") (pinfunction "2_2") (pintype "passive"))
      (node (ref "R17") (pin "2") (pinfunction "2_2") (pintype "passive"))
      (node (ref "R18") (pin "1") (pinfunction "1_1") (pintype "passive"))
      (node (ref "R19") (pin "2") (pinfunction "2_2") (pintype "passive"))
      (node (ref "R22") (pin "1") (pinfunction "1_1") (pintype "passive"))
      (node (ref "R3") (pin "1") (pinfunction "1_1") (pintype "passive"))
      (node (ref "R5") (pin "2") (pinfunction "2_2") (pintype "passive"))
      (node (ref "U$1") (pin "3V3") (pinfunction "3.3V_3V3") (pintype "bidirectional"))
      (node (ref "U$2") (pin "9") (pinfunction "VDDIO_9") (pintype "power_in"))
      (node (ref "U$4") (pin "P$6") (pinfunction "6_P$6") (pintype "passive"))
      (node (ref "U$5") (pin "P$2") (pinfunction "2_P$2") (pintype "passive"))
      (node (ref "U$6") (pin "P$4") (pinfunction "4_P$4") (pintype "passive"))
    )
    (net (code "64") (name "VDD") (class "Default")
      (node (ref "C1") (pin "1") (pinfunction "1_1") (pintype "passive"))
      (node (ref "C5") (pin "1") (pinfunction "1_1") (pintype "passive"))
      (node (ref "C6") (pin "1") (pinfunction "1_1") (pintype "passive"))
      (node (ref "L") (pin "2") (pinfunction "2_2") (pintype "passive"))
      (node (ref "R10") (pin "2") (pinfunction "2_2") (pintype "passive"))
      (node (ref "R11") (pin "2") (pinfunction "2_2") (pintype "passive"))
      (node (ref "R12") (pin "2") (pinfunction "2_2") (pintype "passive"))
      (node (ref "R13") (pin "2") (pinfunction "2_2") (pintype "passive"))
      (node (ref "U$2") (pin "1") (pinfunction "VDD2A_1") (pintype "power_in"))
      (node (ref "U$2") (pin "19") (pinfunction "VDD1A_19") (pintype "power_in"))
      (node (ref "U$3") (pin "12") (pinfunction "YA_12") (pintype "passive"))
      (node (ref "U$3") (pin "4") (pinfunction "P4_4") (pintype "passive"))
      (node (ref "U$3") (pin "5") (pinfunction "P5_5") (pintype "passive"))
      (node (ref "U$3") (pin "9") (pinfunction "GA_9") (pintype "passive"))
    )
    (net (code "65") (name "unconnected-(IC2-N.C.{slash}COMP-Pad7)") (class "Default")
      (node (ref "IC2") (pin "7") (pinfunction "N.C./COMP_7") (pintype "bidirectional"))
    )
    (net (code "66") (name "unconnected-(IC2-~{RESET}-Pad8)") (class "Default")
      (node (ref "IC2") (pin "8") (pinfunction "~{RESET}_8") (pintype "bidirectional"))
    )
    (net (code "67") (name "unconnected-(U$1-GPIO6-PadCLK)") (class "Default")
      (node (ref "U$1") (pin "CLK") (pinfunction "GPIO6_CLK") (pintype "bidirectional"))
    )
    (net (code "68") (name "unconnected-(U$1-GPIO7-PadSD0)") (class "Default")
      (node (ref "U$1") (pin "SD0") (pinfunction "GPIO7_SD0") (pintype "bidirectional"))
    )
    (net (code "69") (name "unconnected-(U$1-GPIO8-PadSD1)") (class "Default")
      (node (ref "U$1") (pin "SD1") (pinfunction "GPIO8_SD1") (pintype "bidirectional"))
    )
    (net (code "70") (name "unconnected-(U$1-GPIO9-PadSD2)") (class "Default")
      (node (ref "U$1") (pin "SD2") (pinfunction "GPIO9_SD2") (pintype "bidirectional"))
    )
    (net (code "71") (name "unconnected-(U$1-GPIO10-PadSD3)") (class "Default")
      (node (ref "U$1") (pin "SD3") (pinfunction "GPIO10_SD3") (pintype "bidirectional"))
    )
    (net (code "72") (name "unconnected-(U$1-GPIO11-PadCMD)") (class "Default")
      (node (ref "U$1") (pin "CMD") (pinfunction "GPIO11_CMD") (pintype "bidirectional"))
    )
    (net (code "73") (name "unconnected-(U$1-GPIO39-PadSENSOR_VN)") (class "Default")
      (node (ref "U$1") (pin "SENSOR_VN") (pinfunction "GPIO39_SENSOR_VN") (pintype "bidirectional"))
    )
    (net (code "74") (name "unconnected-(U$2-XTAL2-Pad4)") (class "Default")
      (node (ref "U$2") (pin "4") (pinfunction "XTAL2_4") (pintype "bidirectional"))
    )
  )
)
